# SCH_Controladora-Exaustao-Chamine.net
KiCad netlist of a schematic drawn in EasyEDA
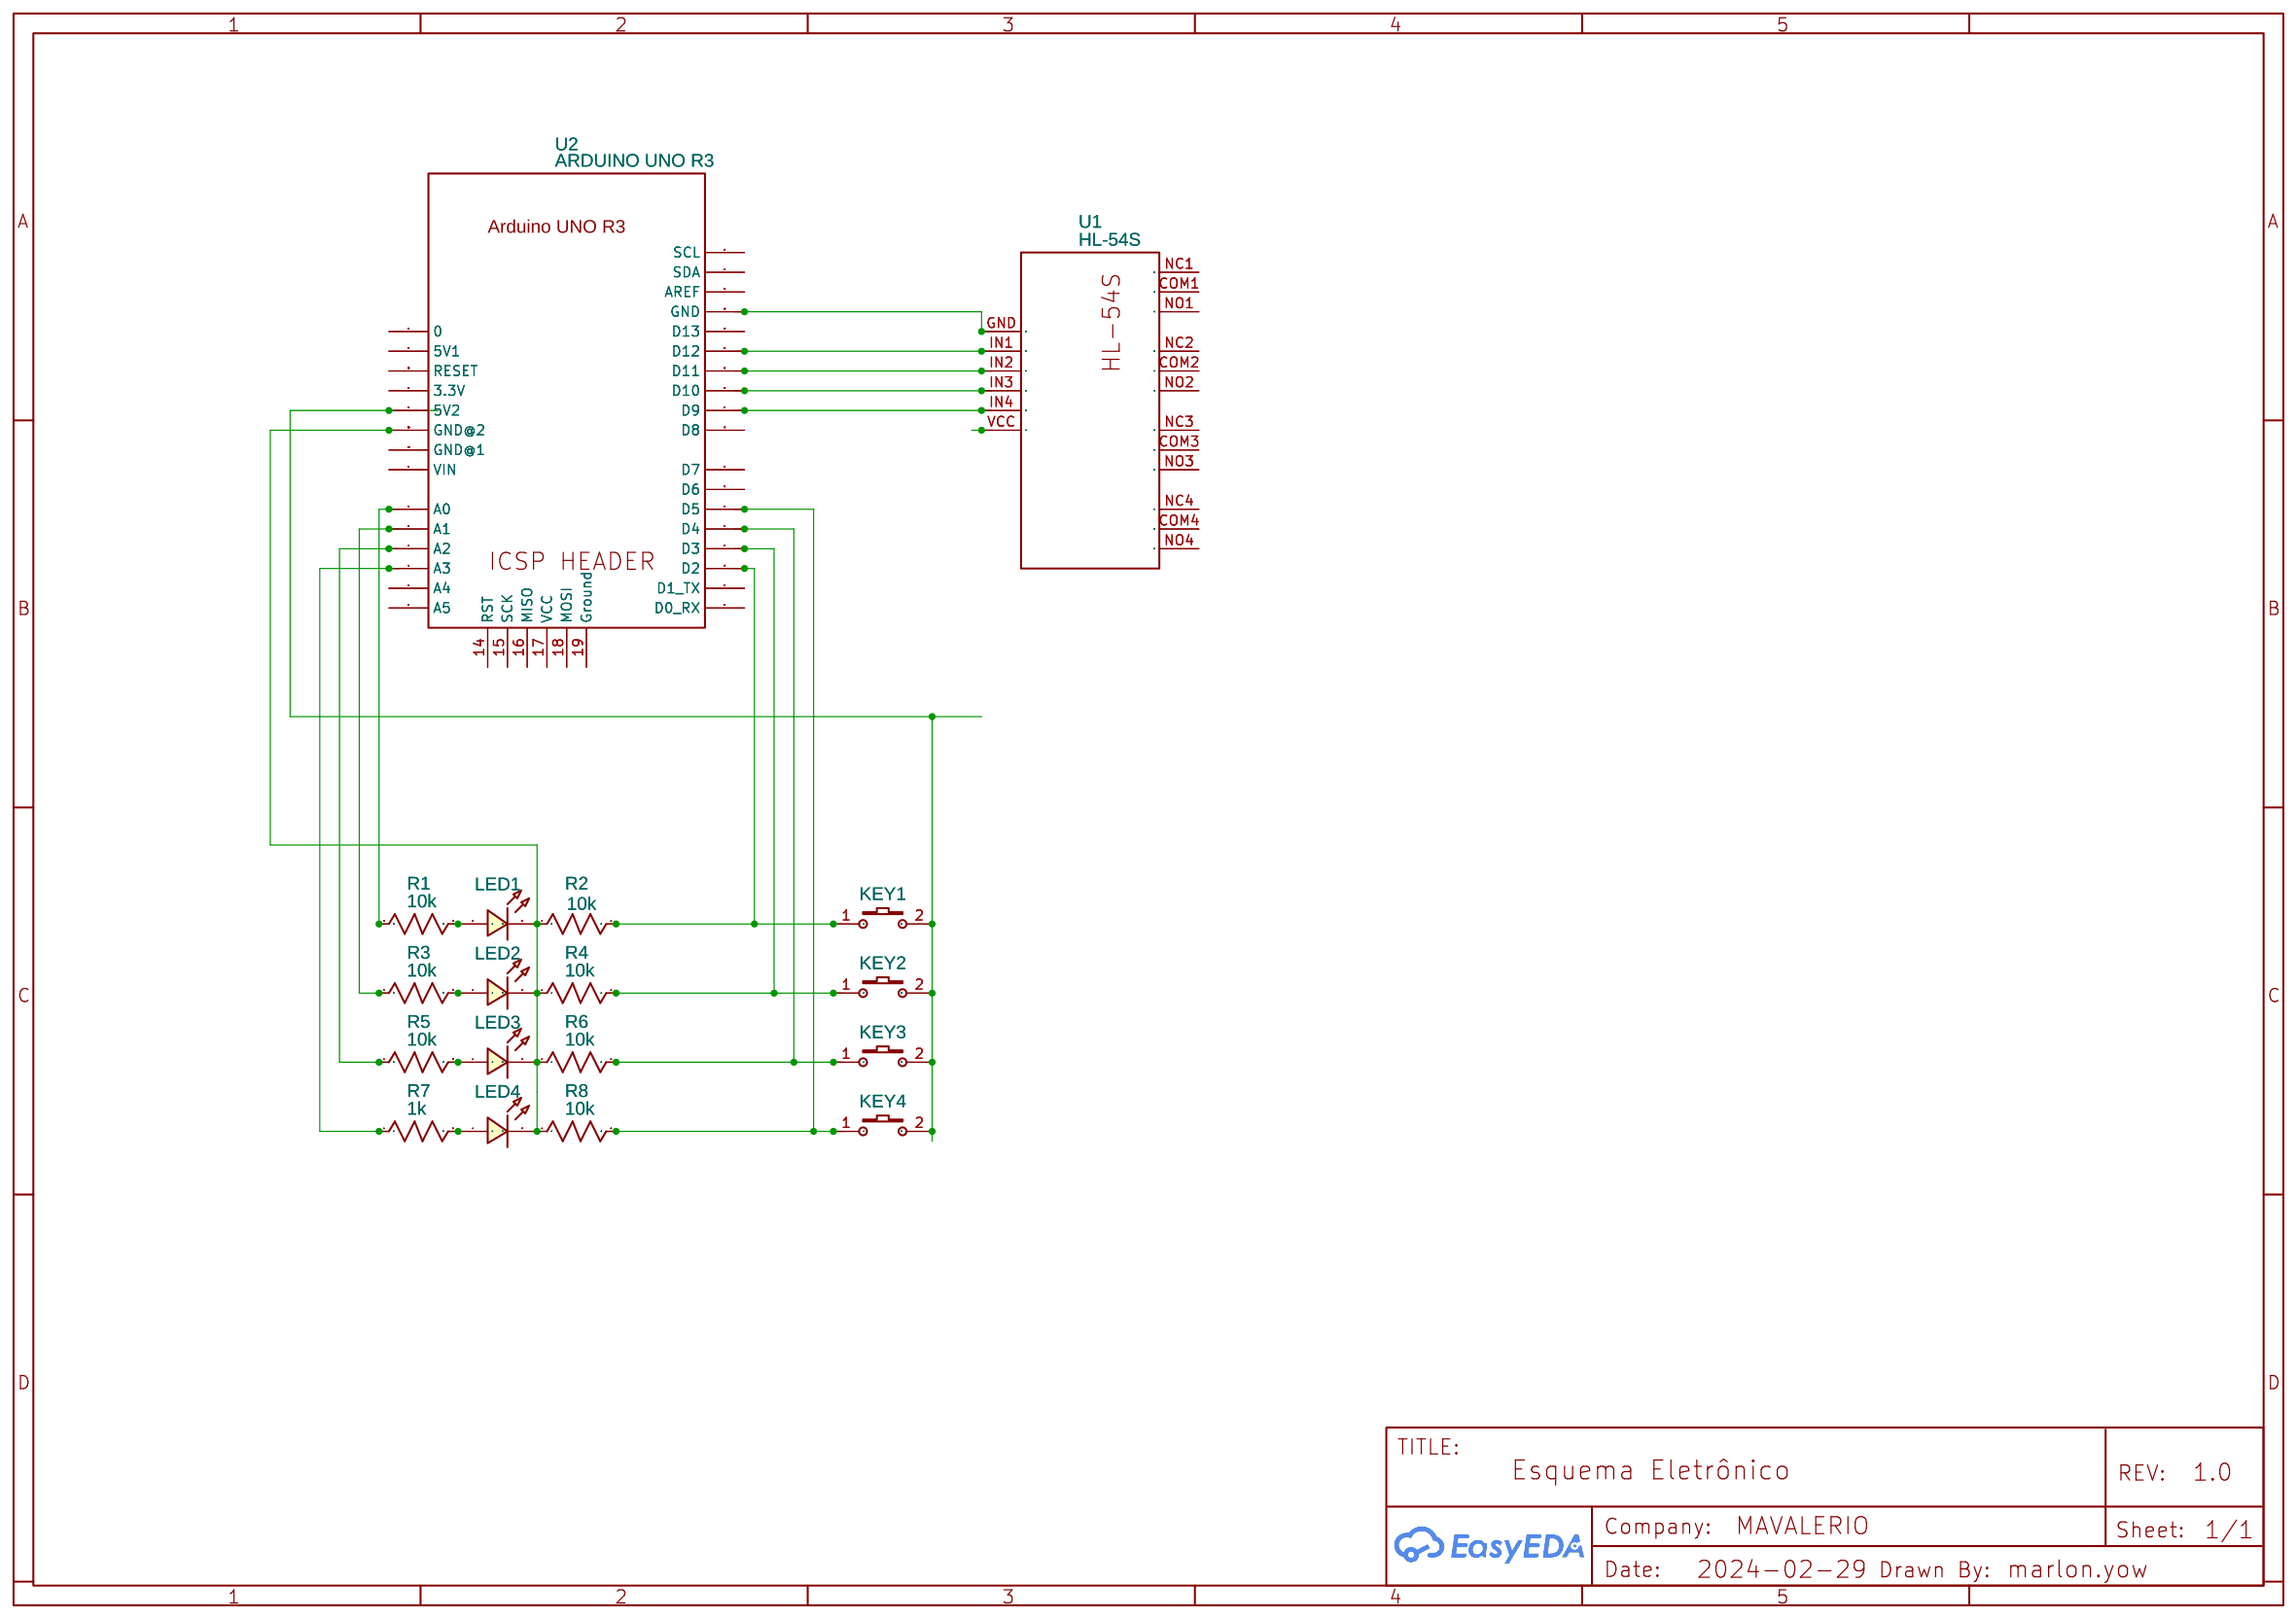
[diagram p0: schematic sheet]

(export (version "E")
  (design (tool "Eeschema 10.0.6"))
  (components
    (comp (ref "KEY1")
      (value "K2-3.6×6.1_SMD")
      (fields (field (name "Manufacturer Part") "K2-1107ST-A4SW-06"))
      (libsource (lib "") (part "K2-3.6×6.1_SMD"))
    )
    (comp (ref "KEY2")
      (value "K2-3.6×6.1_SMD")
      (fields (field (name "Manufacturer Part") "K2-1107ST-A4SW-06"))
      (libsource (lib "") (part "K2-3.6×6.1_SMD"))
    )
    (comp (ref "KEY3")
      (value "K2-3.6×6.1_SMD")
      (fields (field (name "Manufacturer Part") "K2-1107ST-A4SW-06"))
      (libsource (lib "") (part "K2-3.6×6.1_SMD"))
    )
    (comp (ref "KEY4")
      (value "K2-3.6×6.1_SMD")
      (fields (field (name "Manufacturer Part") "K2-1107ST-A4SW-06"))
      (libsource (lib "") (part "K2-3.6×6.1_SMD"))
    )
    (comp (ref "LED1")
      (value "LED-YELLOW")
      (fields
        (field (name "Manufacturer Part") "19-217/R6C-AL1M2VY/3T")
        (field (name "Manufacturer") "EVERLIGHT(台湾亿光)")
      )
      (libsource (lib "") (part "LED-0603_R"))
    )
    (comp (ref "LED2")
      (value "LED-0603_R")
      (fields
        (field (name "Manufacturer Part") "19-217/R6C-AL1M2VY/3T")
        (field (name "Manufacturer") "EVERLIGHT(台湾亿光)")
      )
      (libsource (lib "") (part "LED-0603_R"))
    )
    (comp (ref "LED3")
      (value "LED-0603_R")
      (fields
        (field (name "Manufacturer Part") "19-217/R6C-AL1M2VY/3T")
        (field (name "Manufacturer") "EVERLIGHT(台湾亿光)")
      )
      (libsource (lib "") (part "LED-0603_R"))
    )
    (comp (ref "LED4")
      (value "LED-0603_R")
      (fields
        (field (name "Manufacturer Part") "19-217/R6C-AL1M2VY/3T")
        (field (name "Manufacturer") "EVERLIGHT(台湾亿光)")
      )
      (libsource (lib "") (part "LED-0603_R"))
    )
    (comp (ref "R1") (value "10k") (libsource (lib "") (part "R_0603_US")))
    (comp (ref "R2") (value "10k") (libsource (lib "") (part "R_0603_US")))
    (comp (ref "R3") (value "10k") (libsource (lib "") (part "R_0603_US")))
    (comp (ref "R4") (value "10k") (libsource (lib "") (part "R_0603_US")))
    (comp (ref "R5") (value "10k") (libsource (lib "") (part "R_0603_US")))
    (comp (ref "R6") (value "10k") (libsource (lib "") (part "R_0603_US")))
    (comp (ref "R7") (value "1k") (libsource (lib "") (part "R_0603_US")))
    (comp (ref "R8") (value "10k") (libsource (lib "") (part "R_0603_US")))
    (comp (ref "U1") (value "HL-54S") (libsource (lib "") (part "HL-54S")))
    (comp (ref "U2") (value "ARDUINO UNO R3") (libsource (lib "") (part "ARDUINO UNO R3 BEST")))
  )
  (nets
    (net (code "1") (name "Net-(KEY1-Pad1)") (class "Default")
      (node (ref "KEY1") (pin "1") (pinfunction "1_1") (pintype "unspecified"))
      (node (ref "R2") (pin "2") (pinfunction "2_2") (pintype "unspecified"))
      (node (ref "U2") (pin "D2") (pinfunction "D2_D2") (pintype "unspecified"))
    )
    (net (code "2") (name "Net-(KEY1-Pad2)") (class "Default")
      (node (ref "KEY1") (pin "2") (pinfunction "2_2") (pintype "unspecified"))
      (node (ref "KEY2") (pin "2") (pinfunction "2_2") (pintype "unspecified"))
      (node (ref "KEY3") (pin "2") (pinfunction "2_2") (pintype "unspecified"))
      (node (ref "KEY4") (pin "2") (pinfunction "2_2") (pintype "unspecified"))
      (node (ref "U2") (pin "5V2") (pinfunction "5V2_5V2") (pintype "unspecified"))
    )
    (net (code "3") (name "Net-(KEY2-Pad1)") (class "Default")
      (node (ref "KEY2") (pin "1") (pinfunction "1_1") (pintype "unspecified"))
      (node (ref "R4") (pin "2") (pinfunction "2_2") (pintype "unspecified"))
      (node (ref "U2") (pin "D3") (pinfunction "D3_D3") (pintype "unspecified"))
    )
    (net (code "4") (name "Net-(KEY3-Pad1)") (class "Default")
      (node (ref "KEY3") (pin "1") (pinfunction "1_1") (pintype "unspecified"))
      (node (ref "R6") (pin "2") (pinfunction "2_2") (pintype "unspecified"))
      (node (ref "U2") (pin "D4") (pinfunction "D4_D4") (pintype "unspecified"))
    )
    (net (code "5") (name "Net-(KEY4-Pad1)") (class "Default")
      (node (ref "KEY4") (pin "1") (pinfunction "1_1") (pintype "unspecified"))
      (node (ref "R8") (pin "2") (pinfunction "2_2") (pintype "unspecified"))
      (node (ref "U2") (pin "D5") (pinfunction "D5_D5") (pintype "unspecified"))
    )
    (net (code "6") (name "Net-(LED1-Pad1)") (class "Default")
      (node (ref "LED1") (pin "1") (pinfunction "1_1") (pintype "unspecified"))
      (node (ref "R1") (pin "2") (pinfunction "2_2") (pintype "unspecified"))
    )
    (net (code "7") (name "Net-(LED1-Pad2)") (class "Default")
      (node (ref "LED1") (pin "2") (pinfunction "2_2") (pintype "unspecified"))
      (node (ref "LED2") (pin "2") (pinfunction "2_2") (pintype "unspecified"))
      (node (ref "LED3") (pin "2") (pinfunction "2_2") (pintype "unspecified"))
      (node (ref "LED4") (pin "2") (pinfunction "2_2") (pintype "unspecified"))
      (node (ref "R2") (pin "1") (pinfunction "1_1") (pintype "unspecified"))
      (node (ref "R4") (pin "1") (pinfunction "1_1") (pintype "unspecified"))
      (node (ref "R6") (pin "1") (pinfunction "1_1") (pintype "unspecified"))
      (node (ref "R8") (pin "1") (pinfunction "1_1") (pintype "unspecified"))
      (node (ref "U2") (pin "GND@2") (pinfunction "GND@2_GND@2") (pintype "unspecified"))
    )
    (net (code "8") (name "Net-(LED2-Pad1)") (class "Default")
      (node (ref "LED2") (pin "1") (pinfunction "1_1") (pintype "unspecified"))
      (node (ref "R3") (pin "2") (pinfunction "2_2") (pintype "unspecified"))
    )
    (net (code "9") (name "Net-(LED3-Pad1)") (class "Default")
      (node (ref "LED3") (pin "1") (pinfunction "1_1") (pintype "unspecified"))
      (node (ref "R5") (pin "2") (pinfunction "2_2") (pintype "unspecified"))
    )
    (net (code "10") (name "Net-(LED4-Pad1)") (class "Default")
      (node (ref "LED4") (pin "1") (pinfunction "1_1") (pintype "unspecified"))
      (node (ref "R7") (pin "2") (pinfunction "2_2") (pintype "unspecified"))
    )
    (net (code "11") (name "Net-(R1-Pad1)") (class "Default")
      (node (ref "R1") (pin "1") (pinfunction "1_1") (pintype "unspecified"))
      (node (ref "U2") (pin "A0") (pinfunction "A0_A0") (pintype "unspecified"))
    )
    (net (code "12") (name "Net-(R3-Pad1)") (class "Default")
      (node (ref "R3") (pin "1") (pinfunction "1_1") (pintype "unspecified"))
      (node (ref "U2") (pin "A1") (pinfunction "A1_A1") (pintype "unspecified"))
    )
    (net (code "13") (name "Net-(R5-Pad1)") (class "Default")
      (node (ref "R5") (pin "1") (pinfunction "1_1") (pintype "unspecified"))
      (node (ref "U2") (pin "A2") (pinfunction "A2_A2") (pintype "unspecified"))
    )
    (net (code "14") (name "Net-(R7-Pad1)") (class "Default")
      (node (ref "R7") (pin "1") (pinfunction "1_1") (pintype "unspecified"))
      (node (ref "U2") (pin "A3") (pinfunction "A3_A3") (pintype "unspecified"))
    )
    (net (code "15") (name "Net-(U1-1-PadGND)") (class "Default")
      (node (ref "U1") (pin "GND") (pinfunction "1_GND") (pintype "unspecified"))
      (node (ref "U2") (pin "GND") (pinfunction "GND_GND") (pintype "unspecified"))
    )
    (net (code "16") (name "Net-(U1-1-PadIN1)") (class "Default")
      (node (ref "U1") (pin "IN1") (pinfunction "1_IN1") (pintype "unspecified"))
      (node (ref "U2") (pin "D12") (pinfunction "D12_D12") (pintype "unspecified"))
    )
    (net (code "17") (name "Net-(U1-1-PadIN2)") (class "Default")
      (node (ref "U1") (pin "IN2") (pinfunction "1_IN2") (pintype "unspecified"))
      (node (ref "U2") (pin "D11") (pinfunction "D11_D11") (pintype "unspecified"))
    )
    (net (code "18") (name "Net-(U1-1-PadIN3)") (class "Default")
      (node (ref "U1") (pin "IN3") (pinfunction "1_IN3") (pintype "unspecified"))
      (node (ref "U2") (pin "D10") (pinfunction "D10_D10") (pintype "unspecified"))
    )
    (net (code "19") (name "Net-(U1-1-PadIN4)") (class "Default")
      (node (ref "U1") (pin "IN4") (pinfunction "1_IN4") (pintype "unspecified"))
      (node (ref "U2") (pin "D9") (pinfunction "D9_D9") (pintype "unspecified"))
    )
    (net (code "20") (name "unconnected-(U1-1-PadCOM1)") (class "Default")
      (node (ref "U1") (pin "COM1") (pinfunction "1_COM1") (pintype "unspecified"))
    )
    (net (code "21") (name "unconnected-(U1-1-PadCOM2)") (class "Default")
      (node (ref "U1") (pin "COM2") (pinfunction "1_COM2") (pintype "unspecified"))
    )
    (net (code "22") (name "unconnected-(U1-1-PadCOM3)") (class "Default")
      (node (ref "U1") (pin "COM3") (pinfunction "1_COM3") (pintype "unspecified"))
    )
    (net (code "23") (name "unconnected-(U1-1-PadCOM4)") (class "Default")
      (node (ref "U1") (pin "COM4") (pinfunction "1_COM4") (pintype "unspecified"))
    )
    (net (code "24") (name "unconnected-(U1-1-PadNC1)") (class "Default")
      (node (ref "U1") (pin "NC1") (pinfunction "1_NC1") (pintype "unspecified"))
    )
    (net (code "25") (name "unconnected-(U1-1-PadNC2)") (class "Default")
      (node (ref "U1") (pin "NC2") (pinfunction "1_NC2") (pintype "unspecified"))
    )
    (net (code "26") (name "unconnected-(U1-1-PadNC3)") (class "Default")
      (node (ref "U1") (pin "NC3") (pinfunction "1_NC3") (pintype "unspecified"))
    )
    (net (code "27") (name "unconnected-(U1-1-PadNC4)") (class "Default")
      (node (ref "U1") (pin "NC4") (pinfunction "1_NC4") (pintype "unspecified"))
    )
    (net (code "28") (name "unconnected-(U1-1-PadNO1)") (class "Default")
      (node (ref "U1") (pin "NO1") (pinfunction "1_NO1") (pintype "unspecified"))
    )
    (net (code "29") (name "unconnected-(U1-1-PadNO2)") (class "Default")
      (node (ref "U1") (pin "NO2") (pinfunction "1_NO2") (pintype "unspecified"))
    )
    (net (code "30") (name "unconnected-(U1-1-PadNO3)") (class "Default")
      (node (ref "U1") (pin "NO3") (pinfunction "1_NO3") (pintype "unspecified"))
    )
    (net (code "31") (name "unconnected-(U1-1-PadNO4)") (class "Default")
      (node (ref "U1") (pin "NO4") (pinfunction "1_NO4") (pintype "unspecified"))
    )
    (net (code "32") (name "unconnected-(U1-1-PadVCC)") (class "Default")
      (node (ref "U1") (pin "VCC") (pinfunction "1_VCC") (pintype "unspecified"))
    )
    (net (code "33") (name "unconnected-(U2-D0_RX-PadD0)") (class "Default")
      (node (ref "U2") (pin "D0") (pinfunction "D0_RX_D0") (pintype "unspecified"))
    )
    (net (code "34") (name "unconnected-(U2-D1_TX-PadD1)") (class "Default")
      (node (ref "U2") (pin "D1") (pinfunction "D1_TX_D1") (pintype "unspecified"))
    )
    (net (code "35") (name "unconnected-(U2-Ground-Pad19)") (class "Default")
      (node (ref "U2") (pin "19") (pinfunction "Ground_19") (pintype "unspecified"))
    )
    (net (code "36") (name "unconnected-(U2-MISO-Pad16)") (class "Default")
      (node (ref "U2") (pin "16") (pinfunction "MISO_16") (pintype "unspecified"))
    )
    (net (code "37") (name "unconnected-(U2-MOSI-Pad18)") (class "Default")
      (node (ref "U2") (pin "18") (pinfunction "MOSI_18") (pintype "unspecified"))
    )
    (net (code "38") (name "unconnected-(U2-Pad0)") (class "Default")
      (node (ref "U2") (pin "0") (pinfunction "0_0") (pintype "unspecified"))
    )
    (net (code "39") (name "unconnected-(U2-Pad3.3V)") (class "Default")
      (node (ref "U2") (pin "3.3V") (pinfunction "3.3V_3.3V") (pintype "unspecified"))
    )
    (net (code "40") (name "unconnected-(U2-Pad5V1)") (class "Default")
      (node (ref "U2") (pin "5V1") (pinfunction "5V1_5V1") (pintype "unspecified"))
    )
    (net (code "41") (name "unconnected-(U2-PadA4)") (class "Default")
      (node (ref "U2") (pin "A4") (pinfunction "A4_A4") (pintype "unspecified"))
    )
    (net (code "42") (name "unconnected-(U2-PadA5)") (class "Default")
      (node (ref "U2") (pin "A5") (pinfunction "A5_A5") (pintype "unspecified"))
    )
    (net (code "43") (name "unconnected-(U2-PadAREF)") (class "Default")
      (node (ref "U2") (pin "AREF") (pinfunction "AREF_AREF") (pintype "unspecified"))
    )
    (net (code "44") (name "unconnected-(U2-PadD6)") (class "Default")
      (node (ref "U2") (pin "D6") (pinfunction "D6_D6") (pintype "unspecified"))
    )
    (net (code "45") (name "unconnected-(U2-PadD7)") (class "Default")
      (node (ref "U2") (pin "D7") (pinfunction "D7_D7") (pintype "unspecified"))
    )
    (net (code "46") (name "unconnected-(U2-PadD8)") (class "Default")
      (node (ref "U2") (pin "D8") (pinfunction "D8_D8") (pintype "unspecified"))
    )
    (net (code "47") (name "unconnected-(U2-PadD13)") (class "Default")
      (node (ref "U2") (pin "D13") (pinfunction "D13_D13") (pintype "unspecified"))
    )
    (net (code "48") (name "unconnected-(U2-PadGND@1)") (class "Default")
      (node (ref "U2") (pin "GND@1") (pinfunction "GND@1_GND@1") (pintype "unspecified"))
    )
    (net (code "49") (name "unconnected-(U2-PadRESET)") (class "Default")
      (node (ref "U2") (pin "RESET") (pinfunction "RESET_RESET") (pintype "unspecified"))
    )
    (net (code "50") (name "unconnected-(U2-PadSCL)") (class "Default")
      (node (ref "U2") (pin "SCL") (pinfunction "SCL_SCL") (pintype "unspecified"))
    )
    (net (code "51") (name "unconnected-(U2-PadSDA)") (class "Default")
      (node (ref "U2") (pin "SDA") (pinfunction "SDA_SDA") (pintype "unspecified"))
    )
    (net (code "52") (name "unconnected-(U2-PadVIN)") (class "Default")
      (node (ref "U2") (pin "VIN") (pinfunction "VIN_VIN") (pintype "unspecified"))
    )
    (net (code "53") (name "unconnected-(U2-RST-Pad14)") (class "Default")
      (node (ref "U2") (pin "14") (pinfunction "RST_14") (pintype "unspecified"))
    )
    (net (code "54") (name "unconnected-(U2-SCK-Pad15)") (class "Default")
      (node (ref "U2") (pin "15") (pinfunction "SCK_15") (pintype "unspecified"))
    )
    (net (code "55") (name "unconnected-(U2-VCC-Pad17)") (class "Default")
      (node (ref "U2") (pin "17") (pinfunction "VCC_17") (pintype "unspecified"))
    )
  )
)
